# 3S_Battery_Schematic.net
KiCad netlist of a schematic drawn in Altium Designer
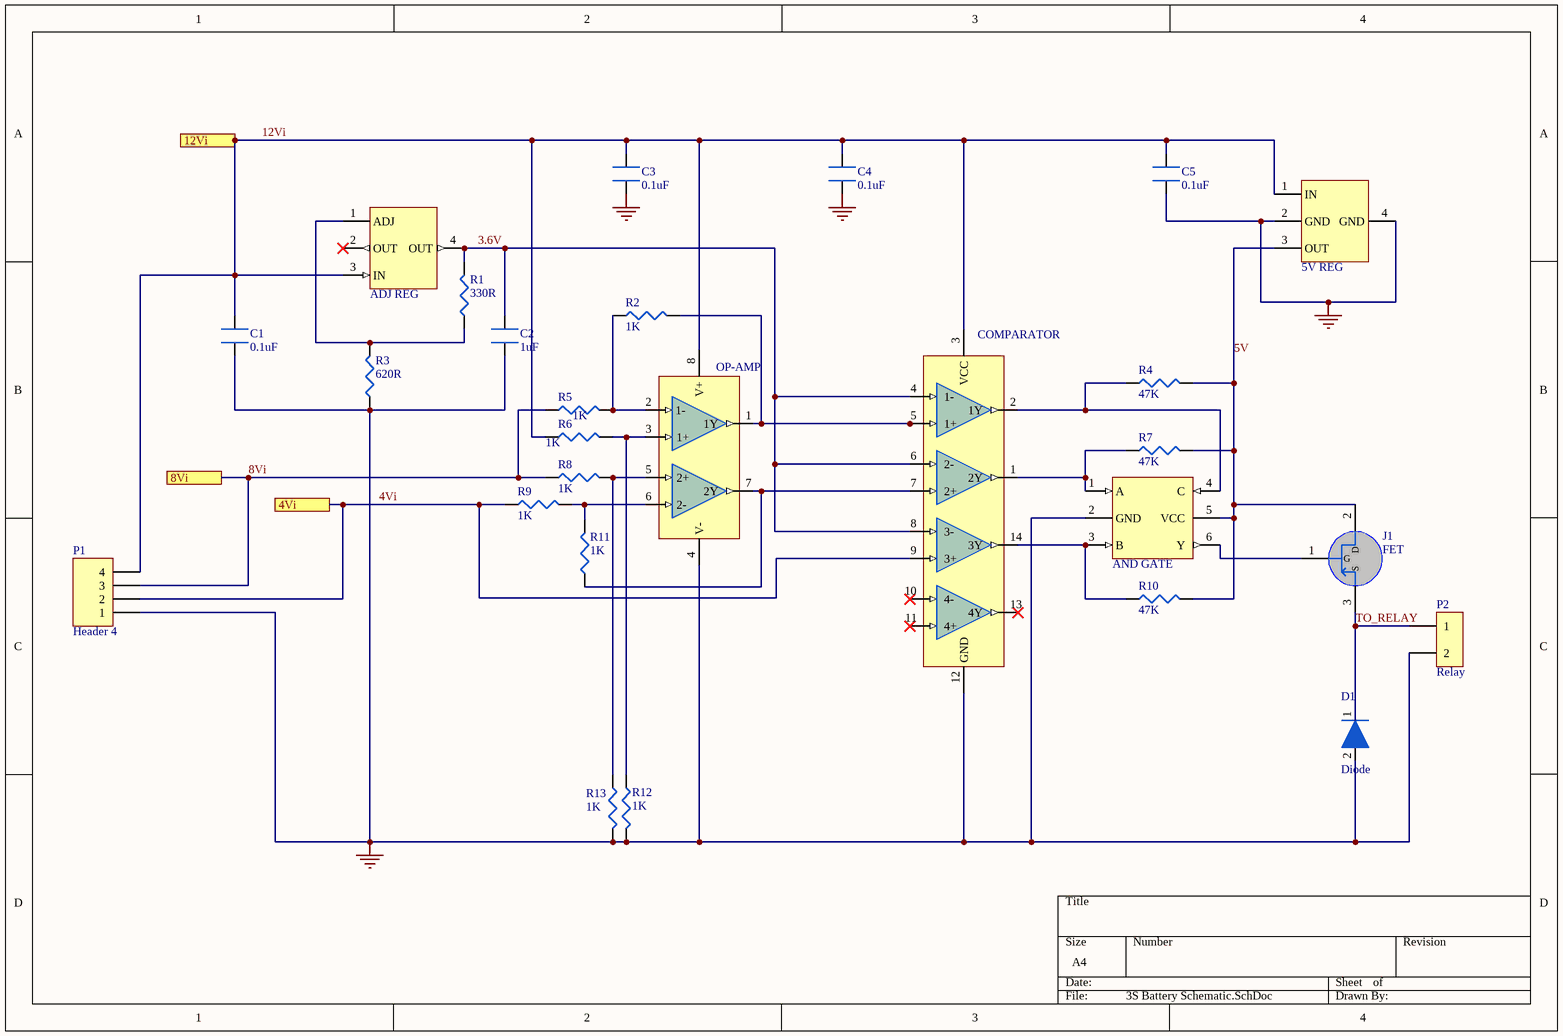
[diagram p0: 3S Battery Schematic.SchDoc]

(export (version "E")
  (design (tool "Eeschema 10.0.6"))
  (components
    (comp (ref "5VREG")
      (value "5V REG")
      (footprint "5VREG")
      (description "IC REG LINEAR 5V 1.5A SOT223-4")
      (fields
        (field (name "MANUFACTURER") "Texas Instruments")
        (field (name "MANUFACTURER PART NUMBER") "LM7805MPX/NOPB")
      )
      (libsource (lib "3S Battery SchemLib") (part "LM7805MPX/NOPB"))
    )
    (comp (ref "ADJ1")
      (value "ADJ REG")
      (footprint "ADJREG")
      (description "TEXAS INSTRUMENTS - LM317DCYR - LINEAR VOLT REG, 1.5A, 1.25V-37V, SOT223")
      (fields
        (field (name "MANUFACTURER") "Texas Instruments")
        (field (name "MANUFACTURER PART NUMBER") "LM317DCYR")
      )
      (libsource (lib "3S Battery SchemLib") (part "LM317DCYR"))
    )
    (comp (ref "AND1")
      (value "AND GATE")
      (footprint "AND3")
      (description "IC GATE AND 1CH 3-INP SC-70-6")
      (fields
        (field (name "MANUFACTURER") "Texas Instruments")
        (field (name "MANUFACTURER PART NUMBER") "SN74LVC1G11DCKR")
      )
      (libsource (lib "3S Battery SchemLib") (part "SN74LVC1G11DCKR"))
    )
    (comp (ref "C1")
      (value "0.1uF")
      (footprint "C1206")
      (description "Kemet 0.1µF ±10% 50V dc X7R Dielectric SMD Ceramic Multilayer Capacitor; 1206 pa")
      (fields
        (field (name "MANUFACTURER") "KEMET")
        (field (name "MANUFACTURER PART NUMBER") "C1206C104K5RAC-TU")
      )
      (libsource (lib "3S Battery SchemLib") (part "C1206C104K5RAC-TU"))
    )
    (comp (ref "C2")
      (value "1uF")
      (footprint "C1206")
      (fields
        (field (name "MANUFACTURER") "KEMET")
        (field (name "MANUFACTURER PART NUMBER") "C1206C105M4RACTU")
        (field (name "TOLERANCE") "20%")
      )
      (libsource (lib "3S Battery SchemLib") (part "C1206C105M4RACTU"))
    )
    (comp (ref "C3")
      (value "0.1uF")
      (footprint "C1206")
      (description "Kemet 0.1µF ±10% 50V dc X7R Dielectric SMD Ceramic Multilayer Capacitor; 1206 pa")
      (fields
        (field (name "MANUFACTURER") "KEMET")
        (field (name "MANUFACTURER PART NUMBER") "C1206C104K5RAC-TU")
      )
      (libsource (lib "3S Battery SchemLib") (part "C1206C104K5RAC-TU"))
    )
    (comp (ref "C4")
      (value "0.1uF")
      (footprint "C1206")
      (description "Kemet 0.1µF ±10% 50V dc X7R Dielectric SMD Ceramic Multilayer Capacitor; 1206 pa")
      (fields
        (field (name "MANUFACTURER") "KEMET")
        (field (name "MANUFACTURER PART NUMBER") "C1206C104K5RAC-TU")
      )
      (libsource (lib "3S Battery SchemLib") (part "C1206C104K5RAC-TU"))
    )
    (comp (ref "C5")
      (value "0.1uF")
      (footprint "C1206")
      (description "Kemet 0.1µF ±10% 50V dc X7R Dielectric SMD Ceramic Multilayer Capacitor; 1206 pa")
      (fields
        (field (name "MANUFACTURER") "KEMET")
        (field (name "MANUFACTURER PART NUMBER") "C1206C104K5RAC-TU")
      )
      (libsource (lib "3S Battery SchemLib") (part "C1206C104K5RAC-TU"))
    )
    (comp (ref "COMP1")
      (value "COMPARATOR")
      (footprint "Comparator")
      (description "Comparator Quad 15V/30V 14-Pin SOIC T/R")
      (fields
        (field (name "MANUFACTURER") "Texas Instruments")
        (field (name "MANUFACTURER PART NUMBER") "LM339DR")
      )
      (libsource (lib "3S Battery SchemLib") (part "LM339DR"))
    )
    (comp (ref "D1")
      (value "Diode")
      (footprint "Diode")
      (fields
        (field (name "MANUFACTURER") "ON Semiconductor / Fairchild")
        (field (name "MANUFACTURER PART NUMBER") "S1B")
      )
      (libsource (lib "3S Battery SchemLib") (part "S1B"))
    )
    (comp (ref "J1")
      (value "FET")
      (footprint "MOSFET")
      (description "N-Channel Enhancement MOSFET SOT-23")
      (fields (field (name "MANUFACTURER") "Diodes") (field (name "MANUFACTURER PART NUMBER") "DMN65D8L-7"))
      (libsource (lib "3S Battery SchemLib") (part "DMN65D8L-7"))
    )
    (comp (ref "OPAMP1")
      (value "OP-AMP")
      (footprint "OPAMP 2-Circuit")
      (description "TEXAS INSTRUMENTS   LMC662AIMX/NOPB   OP-AMP, 1.4MHZ, 1.1V/US, SOIC-8")
      (fields
        (field (name "MANUFACTURER") "Texas Instruments")
        (field (name "MANUFACTURER PART NUMBER") "LMC662AIMX/NOPB")
      )
      (libsource (lib "3S Battery SchemLib") (part "LMC662AIMX/NOPB"))
    )
    (comp (ref "P1")
      (value "Header 4")
      (footprint "HDR1X4")
      (description "Header, 4-Pin")
      (fields (field (name "PUBLISHER") "Altium Limited"))
      (libsource (lib "Miscellaneous Connectors") (part "Header 4"))
    )
    (comp (ref "P2")
      (value "Relay")
      (footprint "HDR1X2")
      (description "Conn Wire to Board HDR 2 POS 2.54mm Solder ST Thru-Hole Bag")
      (fields (field (name "MANUFACTURER") "Molex") (field (name "MANUFACTURER PART NUMBER") "22-29-2021"))
      (libsource (lib "3S Battery SchemLib") (part "22-29-2021"))
    )
    (comp (ref "R1")
      (value "330R")
      (footprint "R1206")
      (description "Surface Mount Thick Film Resistor, RC Series, 330 ohm, 250 mW, - 1%, 200 V, 1206 [3216 Metric]")
      (fields
        (field (name "MANUFACTURER") "Yageo")
        (field (name "MANUFACTURER PART NUMBER") "RC1206FR-07330RL")
      )
      (libsource (lib "3S Battery SchemLib") (part "RC1206FR-07330RL"))
    )
    (comp (ref "R2")
      (value "1K")
      (footprint "R1206")
      (description "RES SMD 1K OHM 5% 1/4W 1206")
      (fields
        (field (name "MANUFACTURER") "Yageo")
        (field (name "MANUFACTURER PART NUMBER") "RC1206JR-071KL")
      )
      (libsource (lib "3S Battery SchemLib") (part "RC1206JR-071KL"))
    )
    (comp (ref "R3")
      (value "620R")
      (footprint "R1206")
      (description "Res Thick Film 1206 620 Ohm 5% 1/4W ±200ppm/C Molded SMD Paper T/R")
      (fields
        (field (name "MANUFACTURER") "Stackpole Electronics")
        (field (name "MANUFACTURER PART NUMBER") "RMCF1206JT620R")
      )
      (libsource (lib "3S Battery SchemLib") (part "RMCF1206JT620R"))
    )
    (comp (ref "R4")
      (value "47K")
      (footprint "R1206")
      (description "RS20-0400S4S4SDAPHHXX.X.")
      (fields
        (field (name "MANUFACTURER") "TE Connectivity")
        (field (name "MANUFACTURER PART NUMBER") "CRGP1206F47K")
      )
      (libsource (lib "3S Battery SchemLib") (part "CRGP1206F47K"))
    )
    (comp (ref "R5")
      (value "1K")
      (footprint "R1206")
      (description "RES SMD 1K OHM 5% 1/4W 1206")
      (fields
        (field (name "MANUFACTURER") "Yageo")
        (field (name "MANUFACTURER PART NUMBER") "RC1206JR-071KL")
      )
      (libsource (lib "3S Battery SchemLib") (part "RC1206JR-071KL"))
    )
    (comp (ref "R6")
      (value "1K")
      (footprint "R1206")
      (description "RES SMD 1K OHM 5% 1/4W 1206")
      (fields
        (field (name "MANUFACTURER") "Yageo")
        (field (name "MANUFACTURER PART NUMBER") "RC1206JR-071KL")
      )
      (libsource (lib "3S Battery SchemLib") (part "RC1206JR-071KL"))
    )
    (comp (ref "R7")
      (value "47K")
      (footprint "R1206")
      (description "RS20-0400S4S4SDAPHHXX.X.")
      (fields
        (field (name "MANUFACTURER") "TE Connectivity")
        (field (name "MANUFACTURER PART NUMBER") "CRGP1206F47K")
      )
      (libsource (lib "3S Battery SchemLib") (part "CRGP1206F47K"))
    )
    (comp (ref "R8")
      (value "1K")
      (footprint "R1206")
      (description "RES SMD 1K OHM 5% 1/4W 1206")
      (fields
        (field (name "MANUFACTURER") "Yageo")
        (field (name "MANUFACTURER PART NUMBER") "RC1206JR-071KL")
      )
      (libsource (lib "3S Battery SchemLib") (part "RC1206JR-071KL"))
    )
    (comp (ref "R9")
      (value "1K")
      (footprint "R1206")
      (description "RES SMD 1K OHM 5% 1/4W 1206")
      (fields
        (field (name "MANUFACTURER") "Yageo")
        (field (name "MANUFACTURER PART NUMBER") "RC1206JR-071KL")
      )
      (libsource (lib "3S Battery SchemLib") (part "RC1206JR-071KL"))
    )
    (comp (ref "R10")
      (value "47K")
      (footprint "R1206")
      (description "RS20-0400S4S4SDAPHHXX.X.")
      (fields
        (field (name "MANUFACTURER") "TE Connectivity")
        (field (name "MANUFACTURER PART NUMBER") "CRGP1206F47K")
      )
      (libsource (lib "3S Battery SchemLib") (part "CRGP1206F47K"))
    )
    (comp (ref "R11")
      (value "1K")
      (footprint "R1206")
      (description "RES SMD 1K OHM 5% 1/4W 1206")
      (fields
        (field (name "MANUFACTURER") "Yageo")
        (field (name "MANUFACTURER PART NUMBER") "RC1206JR-071KL")
      )
      (libsource (lib "3S Battery SchemLib") (part "RC1206JR-071KL"))
    )
    (comp (ref "R12")
      (value "1K")
      (footprint "R1206")
      (description "RES SMD 1K OHM 5% 1/4W 1206")
      (fields
        (field (name "MANUFACTURER") "Yageo")
        (field (name "MANUFACTURER PART NUMBER") "RC1206JR-071KL")
      )
      (libsource (lib "3S Battery SchemLib") (part "RC1206JR-071KL"))
    )
    (comp (ref "R13")
      (value "1K")
      (footprint "R1206")
      (description "RES SMD 1K OHM 5% 1/4W 1206")
      (fields
        (field (name "MANUFACTURER") "Yageo")
        (field (name "MANUFACTURER PART NUMBER") "RC1206JR-071KL")
      )
      (libsource (lib "3S Battery SchemLib") (part "RC1206JR-071KL"))
    )
  )
  (nets
    (net (code "1") (name "/3.6V") (class "Default")
      (node (ref "ADJ1") (pin "4") (pinfunction "OUT_4") (pintype "output"))
      (node (ref "C2") (pin "2") (pinfunction "2_2") (pintype "passive"))
      (node (ref "COMP1") (pin "4") (pinfunction "1-_4") (pintype "input"))
      (node (ref "COMP1") (pin "6") (pinfunction "2-_6") (pintype "input"))
      (node (ref "COMP1") (pin "8") (pinfunction "3-_8") (pintype "input"))
      (node (ref "R1") (pin "2") (pinfunction "2_2") (pintype "passive"))
    )
    (net (code "2") (name "/4Vi") (class "Default")
      (node (ref "COMP1") (pin "9") (pinfunction "3+_9") (pintype "input"))
      (node (ref "P1") (pin "2") (pinfunction "2_2") (pintype "passive"))
      (node (ref "R9") (pin "1") (pinfunction "1_1") (pintype "passive"))
    )
    (net (code "3") (name "/5V") (class "Default")
      (node (ref "5VREG") (pin "3") (pinfunction "OUT_3") (pintype "passive"))
      (node (ref "AND1") (pin "5") (pinfunction "VCC_5") (pintype "power_in"))
      (node (ref "J1") (pin "2") (pinfunction "D_2") (pintype "passive"))
      (node (ref "R10") (pin "2") (pinfunction "2_2") (pintype "passive"))
      (node (ref "R4") (pin "2") (pinfunction "2_2") (pintype "passive"))
      (node (ref "R7") (pin "2") (pinfunction "2_2") (pintype "passive"))
    )
    (net (code "4") (name "/8Vi") (class "Default")
      (node (ref "P1") (pin "3") (pinfunction "3_3") (pintype "passive"))
      (node (ref "R5") (pin "1") (pinfunction "1_1") (pintype "passive"))
      (node (ref "R8") (pin "1") (pinfunction "1_1") (pintype "passive"))
    )
    (net (code "5") (name "/12Vi") (class "Default")
      (node (ref "5VREG") (pin "1") (pinfunction "IN_1") (pintype "passive"))
      (node (ref "ADJ1") (pin "3") (pinfunction "IN_3") (pintype "input"))
      (node (ref "C1") (pin "2") (pinfunction "2_2") (pintype "passive"))
      (node (ref "C3") (pin "2") (pinfunction "2_2") (pintype "passive"))
      (node (ref "C4") (pin "2") (pinfunction "2_2") (pintype "passive"))
      (node (ref "C5") (pin "2") (pinfunction "2_2") (pintype "passive"))
      (node (ref "COMP1") (pin "3") (pinfunction "VCC_3") (pintype "power_in"))
      (node (ref "OPAMP1") (pin "8") (pinfunction "V+_8") (pintype "power_in"))
      (node (ref "P1") (pin "4") (pinfunction "4_4") (pintype "passive"))
      (node (ref "R6") (pin "1") (pinfunction "1_1") (pintype "passive"))
    )
    (net (code "6") (name "/TO_RELAY") (class "Default")
      (node (ref "D1") (pin "1") (pinfunction "1_1") (pintype "passive"))
      (node (ref "J1") (pin "3") (pinfunction "S_3") (pintype "passive"))
      (node (ref "P2") (pin "1") (pinfunction "1_1") (pintype "passive"))
    )
    (net (code "7") (name "GND") (class "Default")
      (node (ref "5VREG") (pin "2") (pinfunction "GND_2") (pintype "passive"))
      (node (ref "5VREG") (pin "4") (pinfunction "GND_4") (pintype "passive"))
      (node (ref "AND1") (pin "2") (pinfunction "GND_2") (pintype "passive"))
      (node (ref "C1") (pin "1") (pinfunction "1_1") (pintype "passive"))
      (node (ref "C2") (pin "1") (pinfunction "1_1") (pintype "passive"))
      (node (ref "C3") (pin "1") (pinfunction "1_1") (pintype "passive"))
      (node (ref "C4") (pin "1") (pinfunction "1_1") (pintype "passive"))
      (node (ref "C5") (pin "1") (pinfunction "1_1") (pintype "passive"))
      (node (ref "COMP1") (pin "12") (pinfunction "GND_12") (pintype "passive"))
      (node (ref "D1") (pin "2") (pinfunction "2_2") (pintype "passive"))
      (node (ref "OPAMP1") (pin "4") (pinfunction "V-_4") (pintype "passive"))
      (node (ref "P1") (pin "1") (pinfunction "1_1") (pintype "passive"))
      (node (ref "P2") (pin "2") (pinfunction "2_2") (pintype "passive"))
      (node (ref "R12") (pin "2") (pinfunction "2_2") (pintype "passive"))
      (node (ref "R13") (pin "2") (pinfunction "2_2") (pintype "passive"))
      (node (ref "R3") (pin "1") (pinfunction "1_1") (pintype "passive"))
    )
    (net (code "8") (name "Net-(ADJ1-ADJ)") (class "Default")
      (node (ref "ADJ1") (pin "1") (pinfunction "ADJ_1") (pintype "passive"))
      (node (ref "R1") (pin "1") (pinfunction "1_1") (pintype "passive"))
      (node (ref "R3") (pin "2") (pinfunction "2_2") (pintype "passive"))
    )
    (net (code "9") (name "Net-(AND1-A)") (class "Default")
      (node (ref "AND1") (pin "1") (pinfunction "A_1") (pintype "input"))
      (node (ref "COMP1") (pin "1") (pinfunction "2Y_1") (pintype "output"))
      (node (ref "R7") (pin "1") (pinfunction "1_1") (pintype "passive"))
    )
    (net (code "10") (name "Net-(AND1-B)") (class "Default")
      (node (ref "AND1") (pin "3") (pinfunction "B_3") (pintype "input"))
      (node (ref "COMP1") (pin "14") (pinfunction "3Y_14") (pintype "output"))
      (node (ref "R10") (pin "1") (pinfunction "1_1") (pintype "passive"))
    )
    (net (code "11") (name "Net-(AND1-C)") (class "Default")
      (node (ref "AND1") (pin "4") (pinfunction "C_4") (pintype "input"))
      (node (ref "COMP1") (pin "2") (pinfunction "1Y_2") (pintype "output"))
      (node (ref "R4") (pin "1") (pinfunction "1_1") (pintype "passive"))
    )
    (net (code "12") (name "Net-(AND1-Y)") (class "Default")
      (node (ref "AND1") (pin "6") (pinfunction "Y_6") (pintype "output"))
      (node (ref "J1") (pin "1") (pinfunction "G_1") (pintype "passive"))
    )
    (net (code "13") (name "Net-(COMP1-1+)") (class "Default")
      (node (ref "COMP1") (pin "5") (pinfunction "1+_5") (pintype "input"))
      (node (ref "OPAMP1") (pin "1") (pinfunction "1Y_1") (pintype "output"))
      (node (ref "R2") (pin "2") (pinfunction "2_2") (pintype "passive"))
    )
    (net (code "14") (name "Net-(COMP1-2+)") (class "Default")
      (node (ref "COMP1") (pin "7") (pinfunction "2+_7") (pintype "input"))
      (node (ref "OPAMP1") (pin "7") (pinfunction "2Y_7") (pintype "output"))
      (node (ref "R11") (pin "1") (pinfunction "1_1") (pintype "passive"))
    )
    (net (code "15") (name "Net-(OPAMP1-1+)") (class "Default")
      (node (ref "OPAMP1") (pin "3") (pinfunction "1+_3") (pintype "input"))
      (node (ref "R12") (pin "1") (pinfunction "1_1") (pintype "passive"))
      (node (ref "R6") (pin "2") (pinfunction "2_2") (pintype "passive"))
    )
    (net (code "16") (name "Net-(OPAMP1-1-)") (class "Default")
      (node (ref "OPAMP1") (pin "2") (pinfunction "1-_2") (pintype "input"))
      (node (ref "R2") (pin "1") (pinfunction "1_1") (pintype "passive"))
      (node (ref "R5") (pin "2") (pinfunction "2_2") (pintype "passive"))
    )
    (net (code "17") (name "Net-(OPAMP1-2+)") (class "Default")
      (node (ref "OPAMP1") (pin "5") (pinfunction "2+_5") (pintype "input"))
      (node (ref "R13") (pin "1") (pinfunction "1_1") (pintype "passive"))
      (node (ref "R8") (pin "2") (pinfunction "2_2") (pintype "passive"))
    )
    (net (code "18") (name "Net-(OPAMP1-2-)") (class "Default")
      (node (ref "OPAMP1") (pin "6") (pinfunction "2-_6") (pintype "input"))
      (node (ref "R11") (pin "2") (pinfunction "2_2") (pintype "passive"))
      (node (ref "R9") (pin "2") (pinfunction "2_2") (pintype "passive"))
    )
    (net (code "19") (name "unconnected-(ADJ1-OUT-Pad2)") (class "Default")
      (node (ref "ADJ1") (pin "2") (pinfunction "OUT_2") (pintype "output+no_connect"))
    )
    (net (code "20") (name "unconnected-(COMP1-4+-Pad11)") (class "Default")
      (node (ref "COMP1") (pin "11") (pinfunction "4+_11") (pintype "input+no_connect"))
    )
    (net (code "21") (name "unconnected-(COMP1-4--Pad10)") (class "Default")
      (node (ref "COMP1") (pin "10") (pinfunction "4-_10") (pintype "input+no_connect"))
    )
    (net (code "22") (name "unconnected-(COMP1-4Y-Pad13)") (class "Default")
      (node (ref "COMP1") (pin "13") (pinfunction "4Y_13") (pintype "output+no_connect"))
    )
  )
)
